# Comparator.net
KiCad netlist of a schematic drawn in Altium Designer
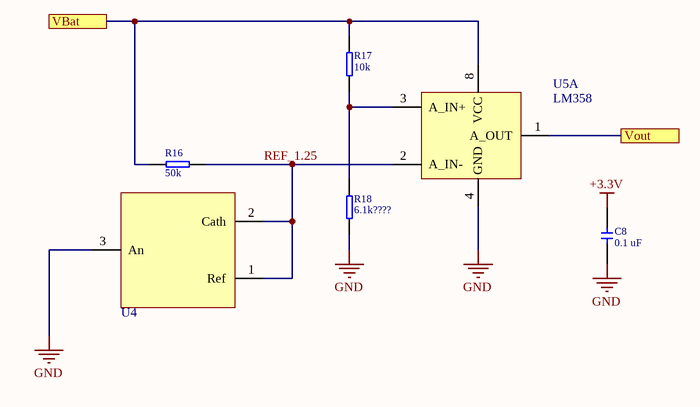
[diagram p0: Comparator.SchDoc]

(export (version "E")
  (design (tool "Eeschema 10.0.6"))
  (components
    (comp (ref "C8")
      (value "0.1 uF")
      (footprint "CERCAP 0402")
      (description "Capacitor")
      (fields (field (name "Comment") "CERCAP 0402 0.1 uF * X7R"))
      (libsource (lib "!main") (part "!Capacitor"))
    )
    (comp (ref "R16")
      (value "50k")
      (footprint "RES 0402")
      (description "Resistor")
      (fields (field (name "Comment") "RES 0402 50k"))
      (libsource (lib "!main") (part "!Resistor"))
    )
    (comp (ref "R17")
      (value "10k")
      (footprint "RES 0402")
      (description "Resistor")
      (fields (field (name "Comment") "RES 0402 10k"))
      (libsource (lib "!main") (part "!Resistor"))
    )
    (comp (ref "R18")
      (value "6.1k????")
      (footprint "RES 0402")
      (description "Resistor")
      (fields (field (name "Comment") "RES 0402 6.1k????"))
      (libsource (lib "!main") (part "!Resistor"))
    )
    (comp (ref "U4")
      (value "Voltage_Ref")
      (footprint "SOT23-3")
      (libsource (lib "analog") (part "Voltage_Ref"))
    )
    (comp (ref "U5")
      (value "LM358")
      (footprint "SO-8")
      (description "Operational amplifier")
      (libsource (lib "analog") (part "DualOpAmp"))
    )
  )
  (nets
    (net (code "1") (name "+3.3V") (class "Default") (node (ref "C8") (pin "2") (pintype "passive")))
    (net (code "2") (name "/REF_1.25") (class "Default")
      (node (ref "R16") (pin "2") (pinfunction "12_2") (pintype "passive"))
      (node (ref "U4") (pin "1") (pinfunction "Ref_1") (pintype "passive"))
      (node (ref "U4") (pin "2") (pinfunction "Cath_2") (pintype "passive"))
      (node (ref "U5") (pin "2") (pinfunction "A_IN-_2") (pintype "passive"))
    )
    (net (code "3") (name "/VBat") (class "Default")
      (node (ref "R16") (pin "1") (pinfunction "11_1") (pintype "passive"))
      (node (ref "R17") (pin "1") (pinfunction "11_1") (pintype "passive"))
      (node (ref "U5") (pin "8") (pinfunction "VCC_8") (pintype "passive"))
    )
    (net (code "4") (name "/Vout") (class "Default")
      (node (ref "U5") (pin "1") (pinfunction "A_OUT_1") (pintype "passive"))
    )
    (net (code "5") (name "GND") (class "Default")
      (node (ref "C8") (pin "1") (pintype "passive"))
      (node (ref "R18") (pin "1") (pinfunction "11_1") (pintype "passive"))
      (node (ref "U4") (pin "3") (pinfunction "An_3") (pintype "passive"))
      (node (ref "U5") (pin "4") (pinfunction "GND_4") (pintype "passive"))
    )
    (net (code "6") (name "Net-(R17-12)") (class "Default")
      (node (ref "R17") (pin "2") (pinfunction "12_2") (pintype "passive"))
      (node (ref "R18") (pin "2") (pinfunction "12_2") (pintype "passive"))
      (node (ref "U5") (pin "3") (pinfunction "A_IN+_3") (pintype "passive"))
    )
  )
)
